# DC_Step-Down_Converter.net
KiCad netlist of a schematic drawn in Altium Designer
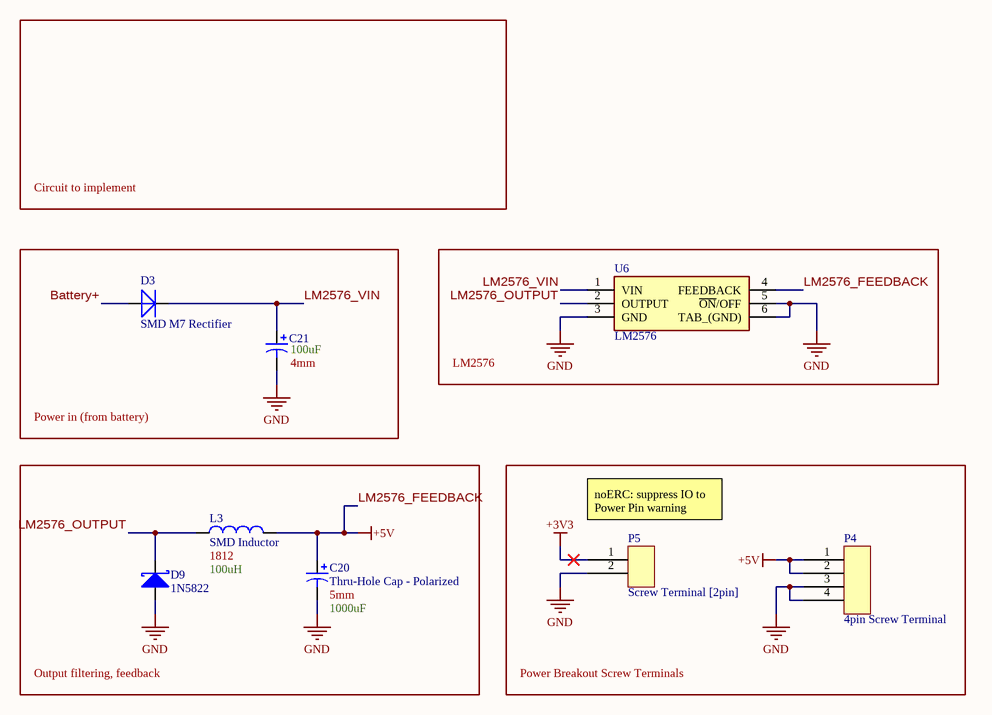
[diagram p0: DC Step-Down Converter.SchDoc]

(export (version "E")
  (design (tool "Eeschema 10.0.6"))
  (components
    (comp (ref "C20")
      (value "Thru-Hole Cap - Polarized")
      (footprint "Thru-Hole Polarized Cap [3.5mm]")
      (fields
        (field (name "MOUSER PART #") "594-MAL214236102E3")
        (field (name "PIN SPACING") "5mm")
        (field (name "CAPACITANCE") "1000uF")
      )
      (libsource (lib "RADM Components") (part "Thru-Hole Cap - Polarized"))
    )
    (comp (ref "C21")
      (value "SMD Cap - Polarized")
      (footprint "SMD Cap - Polarized, 4mm")
      (description "Diameter: 4mm")
      (fields
        (field (name "MOUSER PART #") "667-EEE-FT0J101AR")
        (field (name "CAPACITANCE") "100uF")
        (field (name "DIAMETER") "4mm")
      )
      (libsource (lib "RADM Components") (part "SMD Cap - Polarized"))
    )
    (comp (ref "D3")
      (value "SMD M7 Rectifier")
      (footprint "SMD M7 Rectifier")
      (description "JLC Part #: C95872")
      (fields (field (name "JLC PART #") "C95872"))
      (libsource (lib "RADM Components") (part "SMD M7 Rectifier"))
    )
    (comp (ref "D9")
      (value "1N5822")
      (footprint "1N5822 Schottky Diode")
      (fields (field (name "MOUSER PART #") "511-1N5822"))
      (libsource (lib "RADM Components") (part "1N5822 Schottky Diode"))
    )
    (comp (ref "L3")
      (value "SMD Inductor")
      (footprint "SMD Inductor [1812]")
      (fields
        (field (name "MOUSER PART #") "70-ISC1812ER101J")
        (field (name "SIZE PACKAGE") "1812")
        (field (name "INDUCTANCE") "100uH")
      )
      (libsource (lib "RADM Components") (part "SMD Inductor"))
    )
    (comp (ref "P4")
      (value "4pin Screw Terminal")
      (footprint "Screw Terminal [4pin]")
      (libsource (lib "RADM Components") (part "Screw Terminal [4pin]"))
    )
    (comp (ref "P5")
      (value "Screw Terminal [2pin]")
      (footprint "Screw Terminal [2pin]")
      (libsource (lib "RADM Components") (part "Screw Terminal [2pin]"))
    )
    (comp (ref "U6")
      (value "LM2576")
      (footprint "LM2576 Step Down Converter")
      (libsource (lib "RADM Components") (part "LM2576 Step Down Converter"))
    )
  )
  (nets
    (net (code "1") (name "+3V3") (class "Default") (node (ref "P5") (pin "1") (pintype "power_in")))
    (net (code "2") (name "+5V") (class "Default")
      (node (ref "C20") (pin "1") (pinfunction "1_1") (pintype "passive"))
      (node (ref "L3") (pin "2") (pinfunction "2_2") (pintype "passive"))
      (node (ref "P4") (pin "1") (pintype "power_in"))
      (node (ref "P4") (pin "2") (pintype "power_in"))
      (node (ref "U6") (pin "4") (pinfunction "FEEDBACK_4") (pintype "power_in"))
    )
    (net (code "3") (name "/Battery+") (class "Default")
      (node (ref "D3") (pin "A") (pinfunction "A_A") (pintype "power_in"))
    )
    (net (code "4") (name "/LM2576_OUTPUT") (class "Default")
      (node (ref "D9") (pin "1") (pinfunction "K_1") (pintype "passive"))
      (node (ref "L3") (pin "1") (pinfunction "1_1") (pintype "passive"))
      (node (ref "U6") (pin "2") (pinfunction "OUTPUT_2") (pintype "power_in"))
    )
    (net (code "5") (name "/LM2576_VIN") (class "Default")
      (node (ref "C21") (pin "1") (pinfunction "1_1") (pintype "passive"))
      (node (ref "D3") (pin "C") (pinfunction "C_C") (pintype "power_in"))
      (node (ref "U6") (pin "1") (pinfunction "VIN_1") (pintype "power_in"))
    )
    (net (code "6") (name "GND") (class "Default")
      (node (ref "C20") (pin "2") (pinfunction "2_2") (pintype "passive"))
      (node (ref "C21") (pin "2") (pinfunction "2_2") (pintype "passive"))
      (node (ref "D9") (pin "2") (pinfunction "A_2") (pintype "passive"))
      (node (ref "P4") (pin "3") (pintype "power_in"))
      (node (ref "P4") (pin "4") (pintype "power_in"))
      (node (ref "P5") (pin "2") (pintype "power_in"))
      (node (ref "U6") (pin "3") (pinfunction "GND_3") (pintype "power_in"))
      (node (ref "U6") (pin "5") (pinfunction "~{ON}/OFF_5") (pintype "power_in"))
      (node (ref "U6") (pin "6") (pinfunction "TAB_(GND)_6") (pintype "power_in"))
    )
  )
)
